# ProPrj_FLIGHT-CONTROLLER_2025-07-13-15-4.net
KiCad netlist of a schematic drawn in EasyEDA Pro
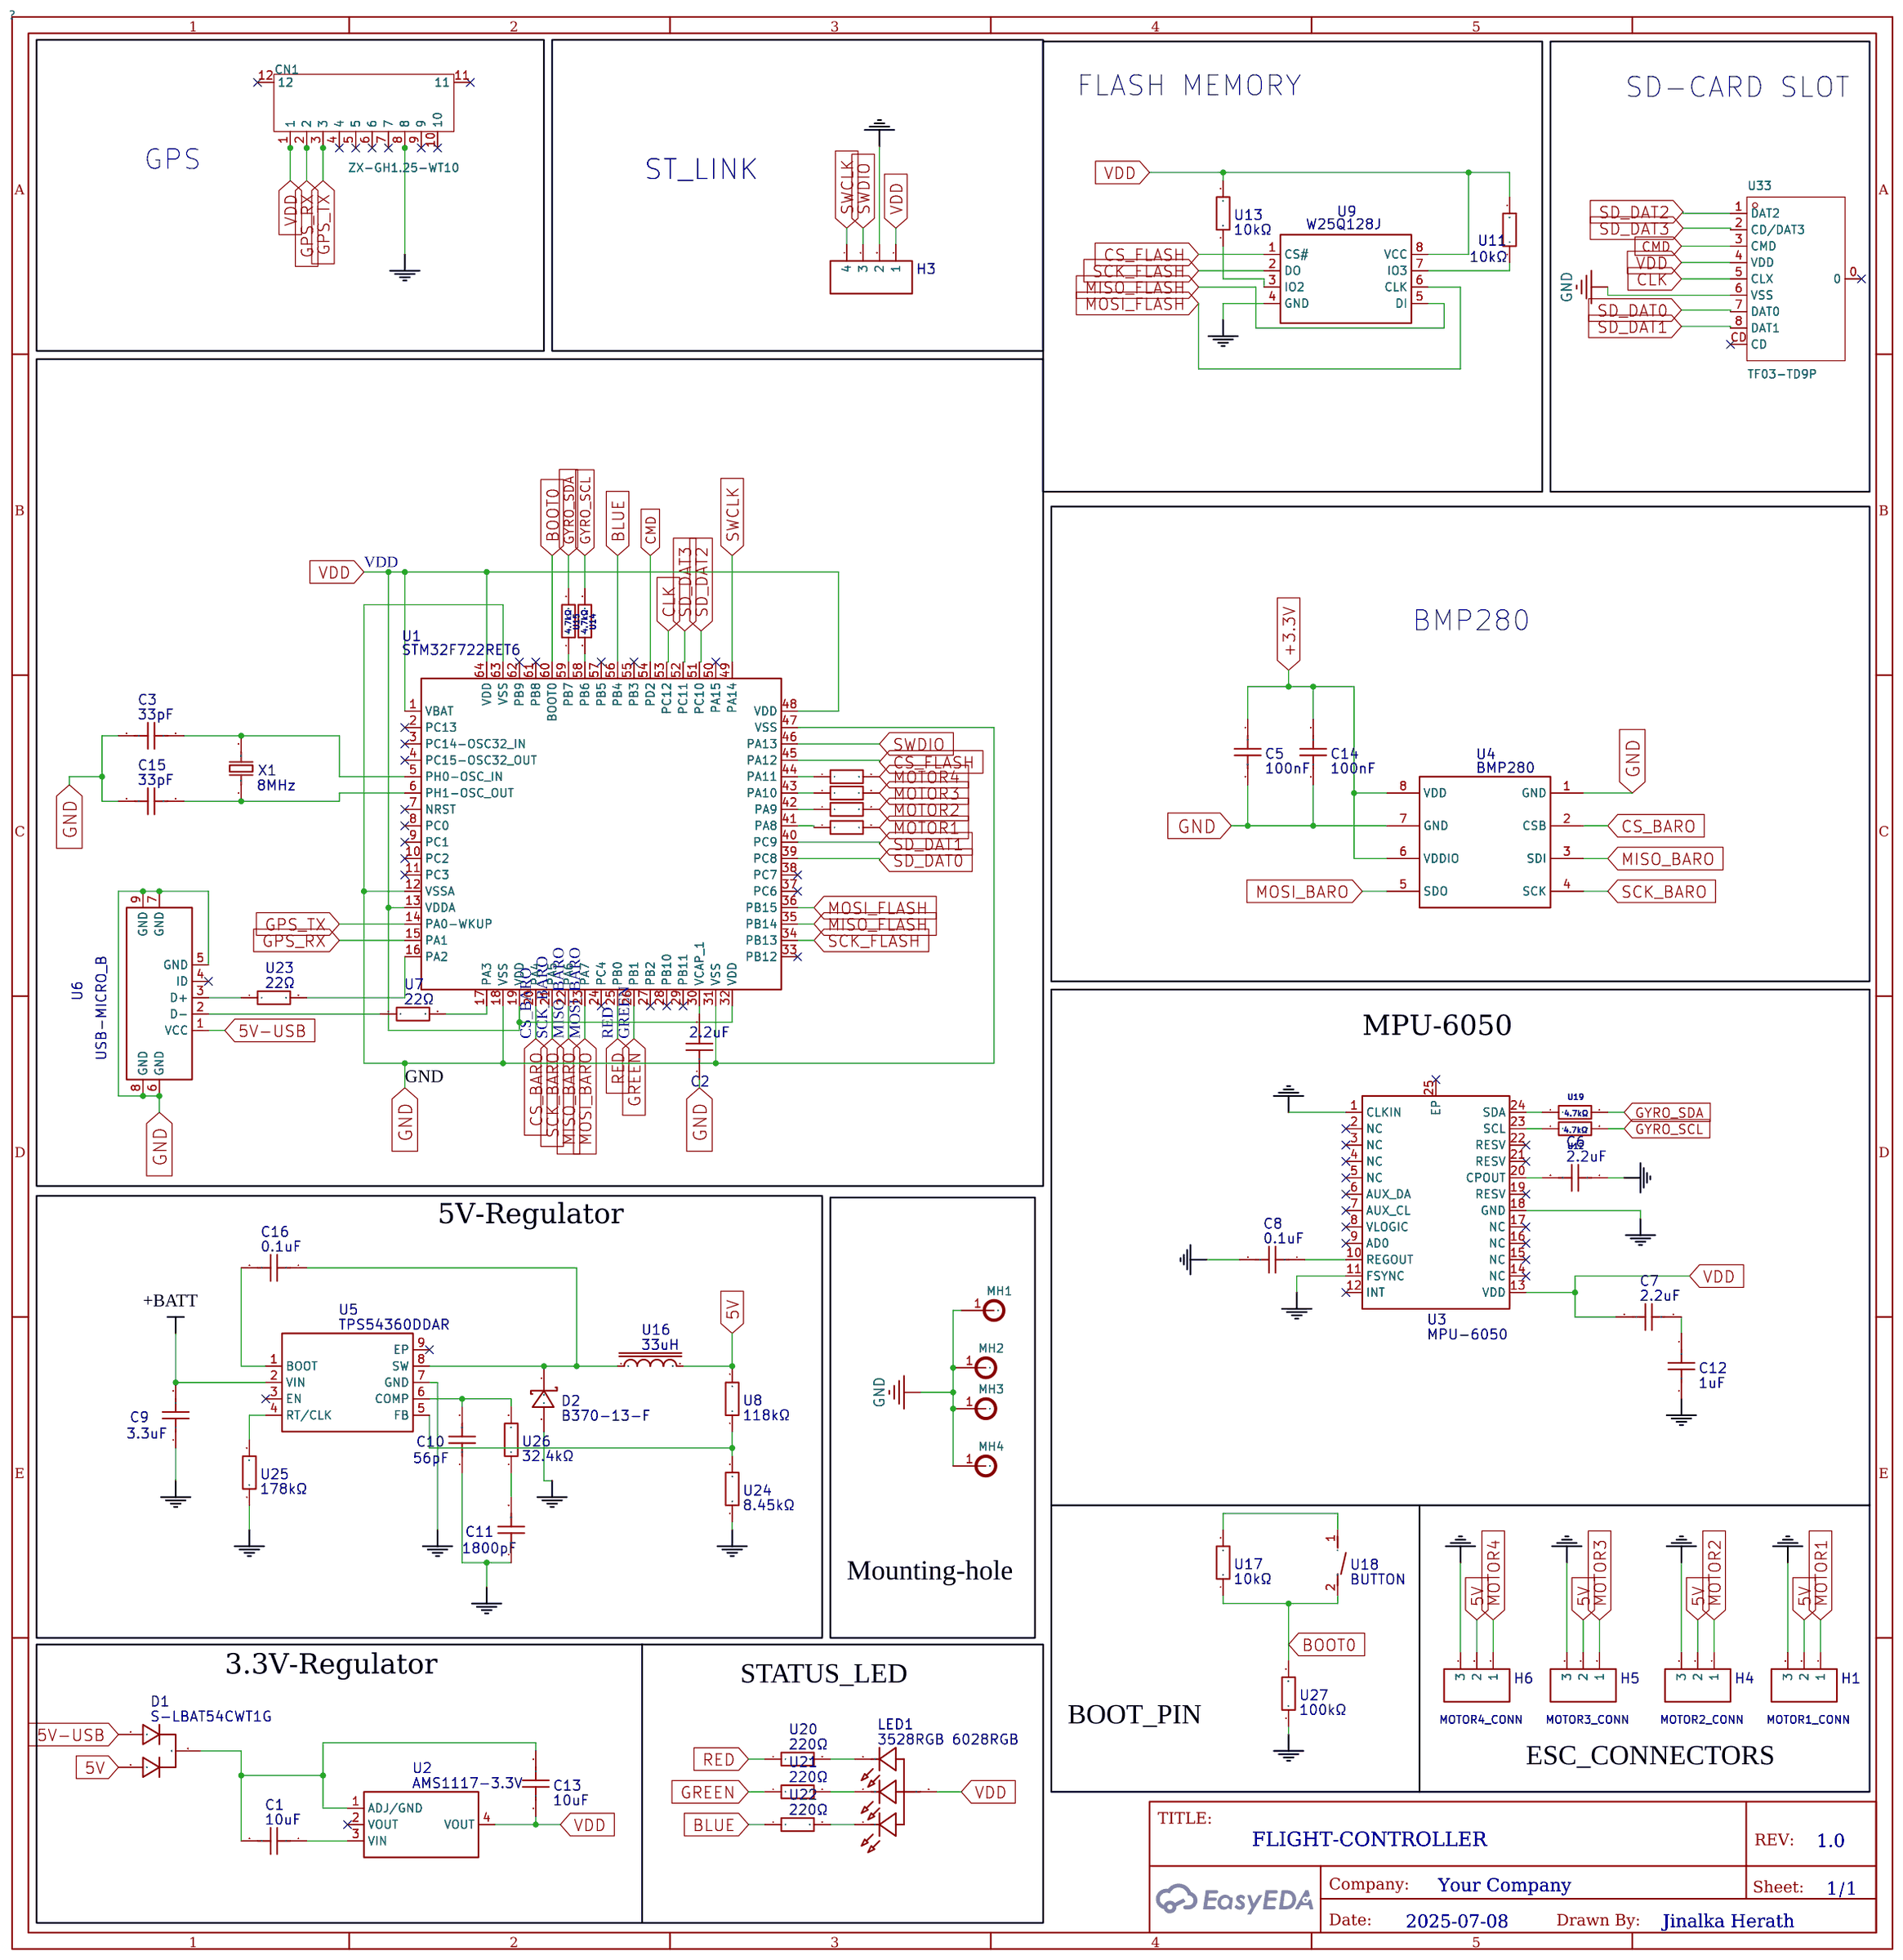
[diagram p0: schematic sheet]

(export (version "E")
  (design (tool "Eeschema 10.0.6"))
  (components
    (comp (ref "C1")
      (value "10uF")
      (footprint "easyedapro:C0603")
      (fields
        (field (name "Manufacturer Part") "C1608CH2A560J080AA")
        (field (name "Manufacturer") "TDK")
        (field (name "Contributor") "lcsc")
      )
      (libsource (lib "easyedapro") (part "10uF"))
    )
    (comp (ref "C2")
      (value "2.2uF")
      (footprint "easyedapro:CAP-SMD_L3.2-W2.5-1")
      (fields
        (field (name "Manufacturer Part") "25MU225MB23225")
        (field (name "Manufacturer") "rubycon(红宝石)")
        (field (name "Contributor") "lcsc")
      )
      (libsource (lib "easyedapro") (part "2.2uF"))
    )
    (comp (ref "C3")
      (value "33pF")
      (footprint "easyedapro:C0603")
      (fields
        (field (name "Manufacturer Part") "C1608CH2A560J080AA")
        (field (name "Manufacturer") "TDK")
        (field (name "Contributor") "lcsc")
      )
      (libsource (lib "easyedapro") (part "33pF"))
    )
    (comp (ref "C5")
      (value "100nF")
      (footprint "easyedapro:C0603")
      (fields
        (field (name "Manufacturer Part") "C1608CH2A560J080AA")
        (field (name "Manufacturer") "TDK")
        (field (name "Contributor") "lcsc")
      )
      (libsource (lib "easyedapro") (part "100nF"))
    )
    (comp (ref "C6")
      (value "2.2uF")
      (footprint "easyedapro:CAP-SMD_L3.2-W2.5-1")
      (fields
        (field (name "Manufacturer Part") "25MU225MB23225")
        (field (name "Manufacturer") "rubycon(红宝石)")
        (field (name "Contributor") "lcsc")
      )
      (libsource (lib "easyedapro") (part "2.2uF"))
    )
    (comp (ref "C7")
      (value "2.2uF")
      (footprint "easyedapro:CAP-SMD_L3.2-W2.5-1")
      (fields
        (field (name "Manufacturer Part") "25MU225MB23225")
        (field (name "Manufacturer") "rubycon(红宝石)")
        (field (name "Contributor") "lcsc")
      )
      (libsource (lib "easyedapro") (part "2.2uF"))
    )
    (comp (ref "C8")
      (value "0.1uF")
      (footprint "easyedapro:C0603")
      (fields
        (field (name "Manufacturer Part") "C1608CH2A560J080AA")
        (field (name "Manufacturer") "TDK")
        (field (name "Contributor") "lcsc")
      )
      (libsource (lib "easyedapro") (part "0.1uF"))
    )
    (comp (ref "C9")
      (value "3.3uF")
      (footprint "easyedapro:C0603")
      (fields
        (field (name "Manufacturer Part") "C1608CH2A560J080AA")
        (field (name "Manufacturer") "TDK")
        (field (name "Contributor") "lcsc")
      )
      (libsource (lib "easyedapro") (part "3.3uF"))
    )
    (comp (ref "C10")
      (value "56pF")
      (footprint "easyedapro:C0603")
      (fields
        (field (name "Manufacturer Part") "C1608CH2A560J080AA")
        (field (name "Manufacturer") "TDK")
        (field (name "Contributor") "lcsc")
      )
      (libsource (lib "easyedapro") (part "56pF"))
    )
    (comp (ref "C11")
      (value "1800pF")
      (footprint "easyedapro:C0603")
      (fields
        (field (name "Manufacturer Part") "C1608CH2A560J080AA")
        (field (name "Manufacturer") "TDK")
        (field (name "Contributor") "lcsc")
      )
      (libsource (lib "easyedapro") (part "1800pF"))
    )
    (comp (ref "C12")
      (value "1uF")
      (footprint "easyedapro:C0603")
      (fields
        (field (name "Manufacturer Part") "C1608CH2A560J080AA")
        (field (name "Manufacturer") "TDK")
        (field (name "Contributor") "lcsc")
      )
      (libsource (lib "easyedapro") (part "1uF"))
    )
    (comp (ref "C13")
      (value "10uF")
      (footprint "easyedapro:C0603")
      (fields
        (field (name "Manufacturer Part") "C1608CH2A560J080AA")
        (field (name "Manufacturer") "TDK")
        (field (name "Contributor") "lcsc")
      )
      (libsource (lib "easyedapro") (part "10uF"))
    )
    (comp (ref "C14")
      (value "100nF")
      (footprint "easyedapro:C0603")
      (fields
        (field (name "Manufacturer Part") "C1608CH2A560J080AA")
        (field (name "Manufacturer") "TDK")
        (field (name "Contributor") "lcsc")
      )
      (libsource (lib "easyedapro") (part "100nF"))
    )
    (comp (ref "C15")
      (value "33pF")
      (footprint "easyedapro:C0603")
      (fields
        (field (name "Manufacturer Part") "C1608CH2A560J080AA")
        (field (name "Manufacturer") "TDK")
        (field (name "Contributor") "lcsc")
      )
      (libsource (lib "easyedapro") (part "33pF"))
    )
    (comp (ref "C16")
      (value "0.1uF")
      (footprint "easyedapro:C0603")
      (fields
        (field (name "Manufacturer Part") "C1608CH2A560J080AA")
        (field (name "Manufacturer") "TDK")
        (field (name "Contributor") "lcsc")
      )
      (libsource (lib "easyedapro") (part "0.1uF"))
    )
    (comp (ref "CN1")
      (value "ZX-GH1.25-WT10")
      (footprint "easyedapro:CONN-SMD_ZX-GH1.25-WT10")
      (fields (field (name "Manufacturer") "Megastar(兆星)"))
      (libsource (lib "easyedapro") (part "ZX-GH1.25-WT10"))
    )
    (comp (ref "D1")
      (value "S-LBAT54CWT1G")
      (footprint "easyedapro:SC-70-3_L2.0-W1.3-P1.30-LS2.1-BR")
      (fields (field (name "Manufacturer") "LRC(乐山无线电)") (field (name "Contributor") "lcsc"))
      (libsource (lib "easyedapro") (part "S-LBAT54CWT1G"))
    )
    (comp (ref "D2")
      (value "B370-13-F")
      (footprint "easyedapro:SMC_L7.1-W6.2-LS8.1-RD")
      (fields (field (name "Manufacturer") "DIODES(美台)") (field (name "Contributor") "LCSC"))
      (libsource (lib "easyedapro") (part "B370-13-F"))
    )
    (comp (ref "H1")
      (value "MOTOR1_CONN")
      (footprint "easyedapro:HDR-F-2.54_1X3")
      (fields (field (name "Contributor") "LCEDA_Lib"))
      (libsource (lib "easyedapro") (part "MOTOR1_CONN"))
    )
    (comp (ref "H3")
      (value "ST_LINK")
      (footprint "easyedapro:HDR-F-2.54_1X4")
      (fields (field (name "Contributor") "LCEDA_Lib"))
      (libsource (lib "easyedapro") (part "ST_LINK"))
    )
    (comp (ref "H4")
      (value "MOTOR2_CONN")
      (footprint "easyedapro:HDR-F-2.54_1X3")
      (fields (field (name "Contributor") "LCEDA_Lib"))
      (libsource (lib "easyedapro") (part "MOTOR2_CONN"))
    )
    (comp (ref "H5")
      (value "MOTOR3_CONN")
      (footprint "easyedapro:HDR-F-2.54_1X3")
      (fields (field (name "Contributor") "LCEDA_Lib"))
      (libsource (lib "easyedapro") (part "MOTOR3_CONN"))
    )
    (comp (ref "H6")
      (value "MOTOR4_CONN")
      (footprint "easyedapro:HDR-F-2.54_1X3")
      (fields (field (name "Contributor") "LCEDA_Lib"))
      (libsource (lib "easyedapro") (part "MOTOR4_CONN"))
    )
    (comp (ref "LED1")
      (value "3528RGB 6028RGB")
      (footprint "easyedapro:LED-SMD_4P-L3.5-W2.8_3528RGB-6028RGB")
      (fields
        (field (name "Manufacturer Part") "3528反贴RGB 6028反贴RGB 缺口蓝色")
        (field (name "Contributor") "lcsc")
      )
      (libsource (lib "easyedapro") (part "3528RGB 6028RGB"))
    )
    (comp (ref "MH1")
      (value "~")
      (footprint "easyedapro:MH_7.5")
      (libsource (lib "easyedapro") (part "MH_7.5"))
    )
    (comp (ref "MH2")
      (value "~")
      (footprint "easyedapro:MH_7.5")
      (libsource (lib "easyedapro") (part "MH_7.5"))
    )
    (comp (ref "MH3")
      (value "~")
      (footprint "easyedapro:MH_7.5")
      (libsource (lib "easyedapro") (part "MH_7.5"))
    )
    (comp (ref "MH4")
      (value "~")
      (footprint "easyedapro:MH_7.5")
      (libsource (lib "easyedapro") (part "MH_7.5"))
    )
    (comp (ref "U1")
      (value "STM32F722RET6")
      (footprint "easyedapro:LQFP-64_L10.0-W10.0-P0.50-LS12.0-BL")
      (fields (field (name "Manufacturer") "ST(意法半导体)") (field (name "Contributor") "LCSC"))
      (libsource (lib "easyedapro") (part "STM32F722RET6"))
    )
    (comp (ref "U2")
      (value "AMS1117-3.3V")
      (footprint "easyedapro:SOT-223-4_L6.5-W3.5-P2.30-LS7.0-BR")
      (fields (field (name "Manufacturer") "WPMtek(维攀)") (field (name "Contributor") "LCSC"))
      (libsource (lib "easyedapro") (part "AMS1117-3.3V"))
    )
    (comp (ref "U3")
      (value "MPU-6050")
      (footprint "easyedapro:QFN-24_L4.0-W4.0-P0.50-BL-EP2.7")
      (fields (field (name "Manufacturer") "TDK InvenSense(应美盛)"))
      (libsource (lib "easyedapro") (part "MPU-6050_C24112"))
    )
    (comp (ref "U4")
      (value "BMP280")
      (footprint "easyedapro:LGA-8_L2.5-W2.0-P0.65_AMP6127")
      (fields (field (name "Manufacturer") "Bosch(博世)"))
      (libsource (lib "easyedapro") (part "BMP280"))
    )
    (comp (ref "U5")
      (value "TPS54360DDAR")
      (footprint "easyedapro:ESOP-8_L4.9-W3.9-P1.27-LS6.0-BL-EP")
      (fields
        (field (name "Manufacturer Part") "TPS54360DDAR(TOKMAS)")
        (field (name "Manufacturer") "Tokmas(托克马斯)")
        (field (name "Contributor") "lcsc")
      )
      (libsource (lib "easyedapro") (part "TPS54360DDAR(TOKMAS)"))
    )
    (comp (ref "U6")
      (value "USB-MICRO_B")
      (footprint "easyedapro:MICRO-USB-SMD_USB-MICRO_B")
      (fields (field (name "Contributor") "LCSC"))
      (libsource (lib "easyedapro") (part "USB-MICRO_B"))
    )
    (comp (ref "U7")
      (value "22Ω")
      (footprint "easyedapro:RES-TH_BD2.3-L3.7-P7.70-D0.9")
      (fields
        (field (name "Manufacturer Part") "MF1/8W-220Ω±1%-ST52")
        (field (name "Manufacturer") "VO(翔胜)")
        (field (name "Contributor") "lcsc")
      )
      (libsource (lib "easyedapro") (part "22Ω"))
    )
    (comp (ref "U8")
      (value "118kΩ")
      (footprint "easyedapro:RES-TH_BD2.3-L3.7-P7.70-D0.9")
      (fields
        (field (name "Manufacturer Part") "MF1/8W-220Ω±1%-ST52")
        (field (name "Manufacturer") "VO(翔胜)")
        (field (name "Contributor") "lcsc")
      )
      (libsource (lib "easyedapro") (part "118kΩ"))
    )
    (comp (ref "U9")
      (value "W25Q128J")
      (footprint "easyedapro:SOIC-8_L5.3-W5.3-P1.27-LS8.0-BL")
      (fields (field (name "Manufacturer Part") "W25Q128JVSIQ") (field (name "Manufacturer") "WINBOND(华邦)"))
      (libsource (lib "easyedapro") (part "W25Q128JVSIQTR"))
    )
    (comp (ref "U11")
      (value "10kΩ")
      (footprint "easyedapro:RES-TH_BD2.3-L3.7-P7.70-D0.9")
      (fields
        (field (name "Manufacturer Part") "MF1/8W-220Ω±1%-ST52")
        (field (name "Manufacturer") "VO(翔胜)")
        (field (name "Contributor") "lcsc")
      )
      (libsource (lib "easyedapro") (part "10kΩ"))
    )
    (comp (ref "U12")
      (value "4.7kΩ")
      (footprint "easyedapro:RES-TH_BD2.3-L3.7-P7.70-D0.9")
      (fields
        (field (name "Manufacturer Part") "MF1/8W-220Ω±1%-ST52")
        (field (name "Manufacturer") "VO(翔胜)")
        (field (name "Contributor") "lcsc")
      )
      (libsource (lib "easyedapro") (part "4.7kΩ"))
    )
    (comp (ref "U13")
      (value "10kΩ")
      (footprint "easyedapro:RES-TH_BD2.3-L3.7-P7.70-D0.9")
      (fields
        (field (name "Manufacturer Part") "MF1/8W-220Ω±1%-ST52")
        (field (name "Manufacturer") "VO(翔胜)")
        (field (name "Contributor") "lcsc")
      )
      (libsource (lib "easyedapro") (part "10kΩ"))
    )
    (comp (ref "U14")
      (value "4.7kΩ")
      (footprint "easyedapro:RES-TH_BD2.3-L3.7-P7.70-D0.9")
      (fields
        (field (name "Manufacturer Part") "MF1/8W-220Ω±1%-ST52")
        (field (name "Manufacturer") "VO(翔胜)")
        (field (name "Contributor") "lcsc")
      )
      (libsource (lib "") (part "4.7kΩ_1"))
    )
    (comp (ref "U15")
      (value "4.7kΩ")
      (footprint "easyedapro:RES-TH_BD2.3-L3.7-P7.70-D0.9")
      (fields
        (field (name "Manufacturer Part") "MF1/8W-220Ω±1%-ST52")
        (field (name "Manufacturer") "VO(翔胜)")
        (field (name "Contributor") "lcsc")
      )
      (libsource (lib "") (part "4.7kΩ_1"))
    )
    (comp (ref "U16")
      (value "33uH")
      (footprint "easyedapro:IND-SMD_L8.5-W8.0_SMS0850")
      (fields
        (field (name "Manufacturer Part") "SMS0850-330MT")
        (field (name "Manufacturer") "LanTu Micro(蓝图微电)")
        (field (name "Contributor") "lcsc")
      )
      (libsource (lib "easyedapro") (part "33uH"))
    )
    (comp (ref "U17")
      (value "10kΩ")
      (footprint "easyedapro:RES-TH_BD2.3-L3.7-P7.70-D0.9")
      (fields
        (field (name "Manufacturer Part") "MF1/8W-220Ω±1%-ST52")
        (field (name "Manufacturer") "VO(翔胜)")
        (field (name "Contributor") "lcsc")
      )
      (libsource (lib "easyedapro") (part "10kΩ"))
    )
    (comp (ref "U18")
      (value "BUTTON")
      (footprint "easyedapro:KEY-SMD_L6.0-W6.0-LS6.6")
      (fields (field (name "Contributor") "lcsc"))
      (libsource (lib "easyedapro") (part "BUTTON"))
    )
    (comp (ref "U19")
      (value "4.7kΩ")
      (footprint "easyedapro:RES-TH_BD2.3-L3.7-P7.70-D0.9")
      (fields
        (field (name "Manufacturer Part") "MF1/8W-220Ω±1%-ST52")
        (field (name "Manufacturer") "VO(翔胜)")
        (field (name "Contributor") "lcsc")
      )
      (libsource (lib "easyedapro") (part "4.7kΩ"))
    )
    (comp (ref "U20")
      (value "220Ω")
      (footprint "easyedapro:RES-TH_BD2.3-L3.7-P7.70-D0.9")
      (fields
        (field (name "Manufacturer Part") "MF1/8W-220Ω±1%-ST52")
        (field (name "Manufacturer") "VO(翔胜)")
        (field (name "Contributor") "lcsc")
      )
      (libsource (lib "easyedapro") (part "220Ω"))
    )
    (comp (ref "U21")
      (value "220Ω")
      (footprint "easyedapro:RES-TH_BD2.3-L3.7-P7.70-D0.9")
      (fields
        (field (name "Manufacturer Part") "MF1/8W-220Ω±1%-ST52")
        (field (name "Manufacturer") "VO(翔胜)")
        (field (name "Contributor") "lcsc")
      )
      (libsource (lib "easyedapro") (part "220Ω"))
    )
    (comp (ref "U22")
      (value "220Ω")
      (footprint "easyedapro:RES-TH_BD2.3-L3.7-P7.70-D0.9")
      (fields
        (field (name "Manufacturer Part") "MF1/8W-220Ω±1%-ST52")
        (field (name "Manufacturer") "VO(翔胜)")
        (field (name "Contributor") "lcsc")
      )
      (libsource (lib "easyedapro") (part "220Ω"))
    )
    (comp (ref "U23")
      (value "22Ω")
      (footprint "easyedapro:RES-TH_BD2.3-L3.7-P7.70-D0.9")
      (fields
        (field (name "Manufacturer Part") "MF1/8W-220Ω±1%-ST52")
        (field (name "Manufacturer") "VO(翔胜)")
        (field (name "Contributor") "lcsc")
      )
      (libsource (lib "easyedapro") (part "22Ω"))
    )
    (comp (ref "U24")
      (value "8.45kΩ")
      (footprint "easyedapro:RES-TH_BD2.3-L3.7-P7.70-D0.9")
      (fields
        (field (name "Manufacturer Part") "MF1/8W-220Ω±1%-ST52")
        (field (name "Manufacturer") "VO(翔胜)")
        (field (name "Contributor") "lcsc")
      )
      (libsource (lib "easyedapro") (part "8.45kΩ"))
    )
    (comp (ref "U25")
      (value "178kΩ")
      (footprint "easyedapro:RES-TH_BD2.3-L3.7-P7.70-D0.9")
      (fields
        (field (name "Manufacturer Part") "MF1/8W-220Ω±1%-ST52")
        (field (name "Manufacturer") "VO(翔胜)")
        (field (name "Contributor") "lcsc")
      )
      (libsource (lib "easyedapro") (part "178kΩ"))
    )
    (comp (ref "U26")
      (value "32.4kΩ")
      (footprint "easyedapro:RES-TH_BD2.3-L3.7-P7.70-D0.9")
      (fields
        (field (name "Manufacturer Part") "MF1/8W-220Ω±1%-ST52")
        (field (name "Manufacturer") "VO(翔胜)")
        (field (name "Contributor") "lcsc")
      )
      (libsource (lib "easyedapro") (part "32.4kΩ"))
    )
    (comp (ref "U27")
      (value "100kΩ")
      (footprint "easyedapro:RES-TH_BD2.3-L3.7-P7.70-D0.9")
      (fields
        (field (name "Manufacturer Part") "MF1/8W-220Ω±1%-ST52")
        (field (name "Manufacturer") "VO(翔胜)")
        (field (name "Contributor") "lcsc")
      )
      (libsource (lib "easyedapro") (part "100kΩ"))
    )
    (comp (ref "U28")
      (value "100Ω")
      (footprint "easyedapro:RES-TH_BD2.3-L3.7-P7.70-D0.9")
      (fields
        (field (name "Manufacturer Part") "MF1/8W-220Ω±1%-ST52")
        (field (name "Manufacturer") "VO(翔胜)")
        (field (name "Contributor") "lcsc")
      )
      (libsource (lib "easyedapro") (part "100Ω"))
    )
    (comp (ref "U29")
      (value "100Ω")
      (footprint "easyedapro:RES-TH_BD2.3-L3.7-P7.70-D0.9")
      (fields
        (field (name "Manufacturer Part") "MF1/8W-220Ω±1%-ST52")
        (field (name "Manufacturer") "VO(翔胜)")
        (field (name "Contributor") "lcsc")
      )
      (libsource (lib "easyedapro") (part "100Ω"))
    )
    (comp (ref "U30")
      (value "100Ω")
      (footprint "easyedapro:RES-TH_BD2.3-L3.7-P7.70-D0.9")
      (fields
        (field (name "Manufacturer Part") "MF1/8W-220Ω±1%-ST52")
        (field (name "Manufacturer") "VO(翔胜)")
        (field (name "Contributor") "lcsc")
      )
      (libsource (lib "easyedapro") (part "100Ω"))
    )
    (comp (ref "U33")
      (value "TF03-TD9P")
      (footprint "easyedapro:CONN-SMD_TF-001A-P")
      (fields (field (name "Manufacturer") "BXCONN(宝讯)"))
      (libsource (lib "easyedapro") (part "TF03-TD9P"))
    )
    (comp (ref "U34")
      (value "100Ω")
      (footprint "easyedapro:RES-TH_BD2.3-L3.7-P7.70-D0.9")
      (fields
        (field (name "Manufacturer Part") "MF1/8W-220Ω±1%-ST52")
        (field (name "Manufacturer") "VO(翔胜)")
        (field (name "Contributor") "lcsc")
      )
      (libsource (lib "easyedapro") (part "100Ω"))
    )
    (comp (ref "X1")
      (value "8MHz")
      (footprint "easyedapro:CRYSTAL-SMD_L3.2-W2.5_3225-8MHZ")
      (fields
        (field (name "Manufacturer Part") "X22EL89COI-111YLC-8M")
        (field (name "Manufacturer") "YXC(扬兴晶振)")
        (field (name "Contributor") "lcsc")
      )
      (libsource (lib "easyedapro") (part "8MHz"))
    )
  )
  (nets
    (net (code "1") (name "+3.3V") (class "Default")
      (node (ref "C14") (pin "1") (pinfunction "1_1") (pintype "unspecified"))
      (node (ref "C5") (pin "1") (pinfunction "1_1") (pintype "unspecified"))
      (node (ref "U4") (pin "6") (pinfunction "VDDIO_6") (pintype "unspecified"))
      (node (ref "U4") (pin "8") (pinfunction "VDD_8") (pintype "unspecified"))
    )
    (net (code "2") (name "+BATT") (class "Default")
      (node (ref "C9") (pin "2") (pinfunction "2_2") (pintype "unspecified"))
      (node (ref "U5") (pin "2") (pinfunction "VIN_2") (pintype "unspecified"))
    )
    (net (code "3") (name "5V") (class "Default")
      (node (ref "D1") (pin "2") (pinfunction "2_2") (pintype "unspecified"))
      (node (ref "H1") (pin "2") (pinfunction "2_2") (pintype "input"))
      (node (ref "H4") (pin "2") (pinfunction "2_2") (pintype "input"))
      (node (ref "H5") (pin "2") (pinfunction "2_2") (pintype "input"))
      (node (ref "H6") (pin "2") (pinfunction "2_2") (pintype "input"))
      (node (ref "U16") (pin "2") (pinfunction "2_2") (pintype "unspecified"))
      (node (ref "U8") (pin "2") (pinfunction "2_2") (pintype "unspecified"))
    )
    (net (code "4") (name "5V-USB") (class "Default")
      (node (ref "D1") (pin "1") (pinfunction "1_1") (pintype "unspecified"))
      (node (ref "U6") (pin "1") (pinfunction "VCC_1") (pintype "unspecified"))
    )
    (net (code "5") (name "BLUE") (class "Default")
      (node (ref "U1") (pin "56") (pinfunction "PB4_56") (pintype "unspecified"))
      (node (ref "U22") (pin "1") (pinfunction "1_1") (pintype "unspecified"))
    )
    (net (code "6") (name "BOOT0") (class "Default")
      (node (ref "U1") (pin "60") (pinfunction "BOOT0_60") (pintype "unspecified"))
      (node (ref "U17") (pin "1") (pinfunction "1_1") (pintype "unspecified"))
      (node (ref "U18") (pin "2") (pinfunction "B_2") (pintype "unspecified"))
      (node (ref "U27") (pin "2") (pinfunction "2_2") (pintype "unspecified"))
    )
    (net (code "7") (name "CLK") (class "Default")
      (node (ref "U1") (pin "53") (pinfunction "PC12_53") (pintype "unspecified"))
      (node (ref "U33") (pin "5") (pinfunction "CLX_5") (pintype "unspecified"))
    )
    (net (code "8") (name "CMD") (class "Default")
      (node (ref "U1") (pin "54") (pinfunction "PD2_54") (pintype "unspecified"))
      (node (ref "U33") (pin "3") (pinfunction "CMD_3") (pintype "unspecified"))
    )
    (net (code "9") (name "CS_BARO") (class "Default")
      (node (ref "U1") (pin "20") (pinfunction "PA4_20") (pintype "unspecified"))
      (node (ref "U4") (pin "2") (pinfunction "CSB_2") (pintype "unspecified"))
    )
    (net (code "10") (name "CS_FLASH") (class "Default")
      (node (ref "U1") (pin "45") (pinfunction "PA12_45") (pintype "unspecified"))
      (node (ref "U9") (pin "1") (pinfunction "CS#_1") (pintype "unspecified"))
    )
    (net (code "11") (name "GND") (class "Default")
      (node (ref "C10") (pin "1") (pinfunction "1_1") (pintype "unspecified"))
      (node (ref "C11") (pin "1") (pinfunction "1_1") (pintype "unspecified"))
      (node (ref "C12") (pin "2") (pinfunction "2_2") (pintype "unspecified"))
      (node (ref "C14") (pin "2") (pinfunction "2_2") (pintype "unspecified"))
      (node (ref "C15") (pin "1") (pinfunction "1_1") (pintype "unspecified"))
      (node (ref "C2") (pin "1") (pinfunction "1_1") (pintype "unspecified"))
      (node (ref "C3") (pin "1") (pinfunction "1_1") (pintype "unspecified"))
      (node (ref "C5") (pin "2") (pinfunction "2_2") (pintype "unspecified"))
      (node (ref "C6") (pin "1") (pinfunction "1_1") (pintype "unspecified"))
      (node (ref "C8") (pin "2") (pinfunction "2_2") (pintype "unspecified"))
      (node (ref "C9") (pin "1") (pinfunction "1_1") (pintype "unspecified"))
      (node (ref "CN1") (pin "8") (pinfunction "8_8") (pintype "unspecified"))
      (node (ref "D2") (pin "2") (pinfunction "A_2") (pintype "unspecified"))
      (node (ref "H1") (pin "3") (pinfunction "3_3") (pintype "input"))
      (node (ref "H3") (pin "2") (pinfunction "2_2") (pintype "unspecified"))
      (node (ref "H4") (pin "3") (pinfunction "3_3") (pintype "input"))
      (node (ref "H5") (pin "3") (pinfunction "3_3") (pintype "input"))
      (node (ref "H6") (pin "3") (pinfunction "3_3") (pintype "input"))
      (node (ref "MH1") (pin "1") (pinfunction "1_1") (pintype "input"))
      (node (ref "MH2") (pin "1") (pinfunction "1_1") (pintype "input"))
      (node (ref "MH3") (pin "1") (pinfunction "1_1") (pintype "input"))
      (node (ref "MH4") (pin "1") (pinfunction "1_1") (pintype "input"))
      (node (ref "U1") (pin "12") (pinfunction "VSSA_12") (pintype "unspecified"))
      (node (ref "U1") (pin "18") (pinfunction "VSS_18") (pintype "unspecified"))
      (node (ref "U1") (pin "31") (pinfunction "VSS_31") (pintype "unspecified"))
      (node (ref "U1") (pin "47") (pinfunction "VSS_47") (pintype "unspecified"))
      (node (ref "U1") (pin "63") (pinfunction "VSS_63") (pintype "unspecified"))
      (node (ref "U24") (pin "1") (pinfunction "1_1") (pintype "unspecified"))
      (node (ref "U25") (pin "1") (pinfunction "1_1") (pintype "unspecified"))
      (node (ref "U27") (pin "1") (pinfunction "1_1") (pintype "unspecified"))
      (node (ref "U3") (pin "1") (pinfunction "CLKIN_1") (pintype "unspecified"))
      (node (ref "U3") (pin "11") (pinfunction "FSYNC_11") (pintype "unspecified"))
      (node (ref "U3") (pin "18") (pinfunction "GND_18") (pintype "unspecified"))
      (node (ref "U33") (pin "6") (pinfunction "VSS_6") (pintype "unspecified"))
      (node (ref "U4") (pin "1") (pinfunction "GND_1") (pintype "unspecified"))
      (node (ref "U4") (pin "7") (pinfunction "GND_7") (pintype "unspecified"))
      (node (ref "U5") (pin "7") (pinfunction "GND_7") (pintype "unspecified"))
      (node (ref "U6") (pin "5") (pinfunction "GND_5") (pintype "unspecified"))
      (node (ref "U6") (pin "6") (pinfunction "GND_6") (pintype "unspecified"))
      (node (ref "U6") (pin "7") (pinfunction "GND_7") (pintype "unspecified"))
      (node (ref "U6") (pin "8") (pinfunction "GND_8") (pintype "unspecified"))
      (node (ref "U6") (pin "9") (pinfunction "GND_9") (pintype "unspecified"))
      (node (ref "U9") (pin "4") (pinfunction "GND_4") (pintype "unspecified"))
    )
    (net (code "12") (name "GPS_RX") (class "Default")
      (node (ref "CN1") (pin "2") (pinfunction "2_2") (pintype "unspecified"))
      (node (ref "U1") (pin "15") (pinfunction "PA1_15") (pintype "unspecified"))
    )
    (net (code "13") (name "GPS_TX") (class "Default")
      (node (ref "CN1") (pin "3") (pinfunction "3_3") (pintype "unspecified"))
      (node (ref "U1") (pin "14") (pinfunction "PA0-WKUP_14") (pintype "unspecified"))
    )
    (net (code "14") (name "GREEN") (class "Default")
      (node (ref "U1") (pin "26") (pinfunction "PB1_26") (pintype "unspecified"))
      (node (ref "U21") (pin "1") (pinfunction "1_1") (pintype "unspecified"))
    )
    (net (code "15") (name "GYRO_SCL") (class "Default")
      (node (ref "U12") (pin "2") (pinfunction "2_2") (pintype "unspecified"))
      (node (ref "U14") (pin "2") (pinfunction "2_2") (pintype "unspecified"))
    )
    (net (code "16") (name "GYRO_SDA") (class "Default")
      (node (ref "U15") (pin "2") (pinfunction "2_2") (pintype "unspecified"))
      (node (ref "U19") (pin "2") (pinfunction "2_2") (pintype "unspecified"))
    )
    (net (code "17") (name "MISO_BARO") (class "Default")
      (node (ref "U1") (pin "22") (pinfunction "PA6_22") (pintype "unspecified"))
      (node (ref "U4") (pin "3") (pinfunction "SDI_3") (pintype "unspecified"))
    )
    (net (code "18") (name "MISO_FLASH") (class "Default")
      (node (ref "U1") (pin "35") (pinfunction "PB14_35") (pintype "unspecified"))
      (node (ref "U9") (pin "5") (pinfunction "DI_5") (pintype "unspecified"))
    )
    (net (code "19") (name "MOSI_BARO") (class "Default")
      (node (ref "U1") (pin "23") (pinfunction "PA7_23") (pintype "unspecified"))
      (node (ref "U4") (pin "5") (pinfunction "SDO_5") (pintype "unspecified"))
    )
    (net (code "20") (name "MOSI_FLASH") (class "Default")
      (node (ref "U1") (pin "36") (pinfunction "PB15_36") (pintype "unspecified"))
      (node (ref "U9") (pin "6") (pinfunction "CLK_6") (pintype "unspecified"))
    )
    (net (code "21") (name "MOTOR1") (class "Default")
      (node (ref "H1") (pin "1") (pinfunction "1_1") (pintype "input"))
      (node (ref "U34") (pin "2") (pinfunction "2_2") (pintype "unspecified"))
    )
    (net (code "22") (name "MOTOR2") (class "Default")
      (node (ref "H4") (pin "1") (pinfunction "1_1") (pintype "input"))
      (node (ref "U29") (pin "2") (pinfunction "2_2") (pintype "unspecified"))
    )
    (net (code "23") (name "MOTOR3") (class "Default")
      (node (ref "H5") (pin "1") (pinfunction "1_1") (pintype "input"))
      (node (ref "U28") (pin "2") (pinfunction "2_2") (pintype "unspecified"))
    )
    (net (code "24") (name "MOTOR4") (class "Default")
      (node (ref "H6") (pin "1") (pinfunction "1_1") (pintype "input"))
      (node (ref "U30") (pin "2") (pinfunction "2_2") (pintype "unspecified"))
    )
    (net (code "25") (name "Net-(C11-Pad2)") (class "Default")
      (node (ref "C11") (pin "2") (pinfunction "2_2") (pintype "unspecified"))
      (node (ref "U26") (pin "1") (pinfunction "1_1") (pintype "unspecified"))
    )
    (net (code "26") (name "Net-(C12-Pad1)") (class "Default")
      (node (ref "C12") (pin "1") (pinfunction "1_1") (pintype "unspecified"))
      (node (ref "C7") (pin "1") (pinfunction "1_1") (pintype "unspecified"))
    )
    (net (code "27") (name "Net-(D2-C)") (class "Default")
      (node (ref "C16") (pin "1") (pinfunction "1_1") (pintype "unspecified"))
      (node (ref "D2") (pin "1") (pinfunction "C_1") (pintype "unspecified"))
      (node (ref "U16") (pin "1") (pinfunction "1_1") (pintype "unspecified"))
      (node (ref "U5") (pin "8") (pinfunction "SW_8") (pintype "unspecified"))
    )
    (net (code "28") (name "Net-(LED1-B)") (class "Default")
      (node (ref "LED1") (pin "1") (pinfunction "B_1") (pintype "unspecified"))
      (node (ref "U21") (pin "2") (pinfunction "2_2") (pintype "unspecified"))
    )
    (net (code "29") (name "Net-(LED1-G)") (class "Default")
      (node (ref "LED1") (pin "4") (pinfunction "G_4") (pintype "unspecified"))
      (node (ref "U22") (pin "2") (pinfunction "2_2") (pintype "unspecified"))
    )
    (net (code "30") (name "Net-(LED1-R)") (class "Default")
      (node (ref "LED1") (pin "2") (pinfunction "R_2") (pintype "unspecified"))
      (node (ref "U20") (pin "2") (pinfunction "2_2") (pintype "unspecified"))
    )
    (net (code "31") (name "Net-(U1-PA2)") (class "Default")
      (node (ref "U1") (pin "16") (pinfunction "PA2_16") (pintype "unspecified"))
      (node (ref "U23") (pin "2") (pinfunction "2_2") (pintype "unspecified"))
    )
    (net (code "32") (name "Net-(U1-PA3)") (class "Default")
      (node (ref "U1") (pin "17") (pinfunction "PA3_17") (pintype "unspecified"))
      (node (ref "U7") (pin "2") (pinfunction "2_2") (pintype "unspecified"))
    )
    (net (code "33") (name "Net-(U1-PA8)") (class "Default")
      (node (ref "U1") (pin "41") (pinfunction "PA8_41") (pintype "unspecified"))
      (node (ref "U34") (pin "1") (pinfunction "1_1") (pintype "unspecified"))
    )
    (net (code "34") (name "Net-(U1-PA9)") (class "Default")
      (node (ref "U1") (pin "42") (pinfunction "PA9_42") (pintype "unspecified"))
      (node (ref "U29") (pin "1") (pinfunction "1_1") (pintype "unspecified"))
    )
    (net (code "35") (name "Net-(U1-PA10)") (class "Default")
      (node (ref "U1") (pin "43") (pinfunction "PA10_43") (pintype "unspecified"))
      (node (ref "U28") (pin "1") (pinfunction "1_1") (pintype "unspecified"))
    )
    (net (code "36") (name "Net-(U1-PA11)") (class "Default")
      (node (ref "U1") (pin "44") (pinfunction "PA11_44") (pintype "unspecified"))
      (node (ref "U30") (pin "1") (pinfunction "1_1") (pintype "unspecified"))
    )
    (net (code "37") (name "Net-(U1-PB6)") (class "Default")
      (node (ref "U1") (pin "58") (pinfunction "PB6_58") (pintype "unspecified"))
      (node (ref "U14") (pin "1") (pinfunction "1_1") (pintype "unspecified"))
    )
    (net (code "38") (name "Net-(U1-PB7)") (class "Default")
      (node (ref "U1") (pin "59") (pinfunction "PB7_59") (pintype "unspecified"))
      (node (ref "U15") (pin "1") (pinfunction "1_1") (pintype "unspecified"))
    )
    (net (code "39") (name "Net-(U1-PH0-OSC_IN)") (class "Default")
      (node (ref "C3") (pin "2") (pinfunction "2_2") (pintype "unspecified"))
      (node (ref "U1") (pin "5") (pinfunction "PH0-OSC_IN_5") (pintype "unspecified"))
      (node (ref "X1") (pin "2") (pinfunction "2_2") (pintype "unspecified"))
    )
    (net (code "40") (name "Net-(U1-PH1-OSC_OUT)") (class "Default")
      (node (ref "C15") (pin "2") (pinfunction "2_2") (pintype "unspecified"))
      (node (ref "U1") (pin "6") (pinfunction "PH1-OSC_OUT_6") (pintype "unspecified"))
      (node (ref "X1") (pin "1") (pinfunction "1_1") (pintype "unspecified"))
    )
    (net (code "41") (name "Net-(U1-VCAP_1)") (class "Default")
      (node (ref "C2") (pin "2") (pinfunction "2_2") (pintype "unspecified"))
      (node (ref "U1") (pin "30") (pinfunction "VCAP_1_30") (pintype "unspecified"))
    )
    (net (code "42") (name "Net-(U2-ADJ{slash}GND)") (class "Default")
      (node (ref "C1") (pin "2") (pinfunction "2_2") (pintype "unspecified"))
      (node (ref "C13") (pin "1") (pinfunction "1_1") (pintype "unspecified"))
      (node (ref "D1") (pin "3") (pinfunction "3_3") (pintype "unspecified"))
      (node (ref "U2") (pin "1") (pinfunction "ADJ/GND_1") (pintype "unspecified"))
    )
    (net (code "43") (name "Net-(U2-VIN)") (class "Default")
      (node (ref "C1") (pin "1") (pinfunction "1_1") (pintype "unspecified"))
      (node (ref "U2") (pin "3") (pinfunction "VIN_3") (pintype "unspecified"))
    )
    (net (code "44") (name "Net-(U3-CPOUT)") (class "Default")
      (node (ref "C6") (pin "2") (pinfunction "2_2") (pintype "unspecified"))
      (node (ref "U3") (pin "20") (pinfunction "CPOUT_20") (pintype "unspecified"))
    )
    (net (code "45") (name "Net-(U3-REGOUT)") (class "Default")
      (node (ref "C8") (pin "1") (pinfunction "1_1") (pintype "unspecified"))
      (node (ref "U3") (pin "10") (pinfunction "REGOUT_10") (pintype "unspecified"))
    )
    (net (code "46") (name "Net-(U3-SCL)") (class "Default")
      (node (ref "U12") (pin "1") (pinfunction "1_1") (pintype "unspecified"))
      (node (ref "U3") (pin "23") (pinfunction "SCL_23") (pintype "unspecified"))
    )
    (net (code "47") (name "Net-(U3-SDA)") (class "Default")
      (node (ref "U19") (pin "1") (pinfunction "1_1") (pintype "unspecified"))
      (node (ref "U3") (pin "24") (pinfunction "SDA_24") (pintype "unspecified"))
    )
    (net (code "48") (name "Net-(U5-BOOT)") (class "Default")
      (node (ref "C16") (pin "2") (pinfunction "2_2") (pintype "unspecified"))
      (node (ref "U5") (pin "1") (pinfunction "BOOT_1") (pintype "unspecified"))
    )
    (net (code "49") (name "Net-(U5-COMP)") (class "Default")
      (node (ref "C10") (pin "2") (pinfunction "2_2") (pintype "unspecified"))
      (node (ref "U26") (pin "2") (pinfunction "2_2") (pintype "unspecified"))
      (node (ref "U5") (pin "6") (pinfunction "COMP_6") (pintype "unspecified"))
    )
    (net (code "50") (name "Net-(U5-FB)") (class "Default")
      (node (ref "U24") (pin "2") (pinfunction "2_2") (pintype "unspecified"))
      (node (ref "U5") (pin "5") (pinfunction "FB_5") (pintype "unspecified"))
      (node (ref "U8") (pin "1") (pinfunction "1_1") (pintype "unspecified"))
    )
    (net (code "51") (name "Net-(U5-RT{slash}CLK)") (class "Default")
      (node (ref "U25") (pin "2") (pinfunction "2_2") (pintype "unspecified"))
      (node (ref "U5") (pin "4") (pinfunction "RT/CLK_4") (pintype "unspecified"))
    )
    (net (code "52") (name "Net-(U6-D+)") (class "Default")
      (node (ref "U23") (pin "1") (pinfunction "1_1") (pintype "unspecified"))
      (node (ref "U6") (pin "3") (pinfunction "D+_3") (pintype "unspecified"))
    )
    (net (code "53") (name "Net-(U6-D-)") (class "Default")
      (node (ref "U6") (pin "2") (pinfunction "D-_2") (pintype "unspecified"))
      (node (ref "U7") (pin "1") (pinfunction "1_1") (pintype "unspecified"))
    )
    (net (code "54") (name "Net-(U9-IO2)") (class "Default")
      (node (ref "U13") (pin "1") (pinfunction "1_1") (pintype "unspecified"))
      (node (ref "U9") (pin "3") (pinfunction "IO2_3") (pintype "unspecified"))
    )
    (net (code "55") (name "Net-(U9-IO3)") (class "Default")
      (node (ref "U11") (pin "1") (pinfunction "1_1") (pintype "unspecified"))
      (node (ref "U9") (pin "7") (pinfunction "IO3_7") (pintype "unspecified"))
    )
    (net (code "56") (name "Net-(U18-A)") (class "Default")
      (node (ref "U17") (pin "2") (pinfunction "2_2") (pintype "unspecified"))
      (node (ref "U18") (pin "1") (pinfunction "A_1") (pintype "unspecified"))
    )
    (net (code "57") (name "RED") (class "Default")
      (node (ref "U1") (pin "25") (pinfunction "PB0_25") (pintype "unspecified"))
      (node (ref "U20") (pin "1") (pinfunction "1_1") (pintype "unspecified"))
    )
    (net (code "58") (name "SCK_BARO") (class "Default")
      (node (ref "U1") (pin "21") (pinfunction "PA5_21") (pintype "unspecified"))
      (node (ref "U4") (pin "4") (pinfunction "SCK_4") (pintype "unspecified"))
    )
    (net (code "59") (name "SCK_FLASH") (class "Default")
      (node (ref "U1") (pin "34") (pinfunction "PB13_34") (pintype "unspecified"))
      (node (ref "U9") (pin "2") (pinfunction "DO_2") (pintype "unspecified"))
    )
    (net (code "60") (name "SD_DAT0") (class "Default")
      (node (ref "U1") (pin "39") (pinfunction "PC8_39") (pintype "unspecified"))
      (node (ref "U33") (pin "7") (pinfunction "DAT0_7") (pintype "unspecified"))
    )
    (net (code "61") (name "SD_DAT1") (class "Default")
      (node (ref "U1") (pin "40") (pinfunction "PC9_40") (pintype "unspecified"))
      (node (ref "U33") (pin "8") (pinfunction "DAT1_8") (pintype "unspecified"))
    )
    (net (code "62") (name "SD_DAT2") (class "Default")
      (node (ref "U1") (pin "51") (pinfunction "PC10_51") (pintype "unspecified"))
      (node (ref "U33") (pin "1") (pinfunction "DAT2_1") (pintype "unspecified"))
    )
    (net (code "63") (name "SD_DAT3") (class "Default")
      (node (ref "U1") (pin "52") (pinfunction "PC11_52") (pintype "unspecified"))
      (node (ref "U33") (pin "2") (pinfunction "CD/DAT3_2") (pintype "unspecified"))
    )
    (net (code "64") (name "SWCLK") (class "Default")
      (node (ref "H3") (pin "4") (pinfunction "4_4") (pintype "unspecified"))
      (node (ref "U1") (pin "49") (pinfunction "PA14_49") (pintype "unspecified"))
    )
    (net (code "65") (name "SWDIO") (class "Default")
      (node (ref "H3") (pin "3") (pinfunction "3_3") (pintype "unspecified"))
      (node (ref "U1") (pin "46") (pinfunction "PA13_46") (pintype "unspecified"))
    )
    (net (code "66") (name "VDD") (class "Default")
      (node (ref "C13") (pin "2") (pinfunction "2_2") (pintype "unspecified"))
      (node (ref "C7") (pin "2") (pinfunction "2_2") (pintype "unspecified"))
      (node (ref "CN1") (pin "1") (pinfunction "1_1") (pintype "unspecified"))
      (node (ref "H3") (pin "1") (pinfunction "1_1") (pintype "unspecified"))
      (node (ref "LED1") (pin "3") (pinfunction "A_3") (pintype "unspecified"))
      (node (ref "U1") (pin "1") (pinfunction "VBAT_1") (pintype "unspecified"))
      (node (ref "U1") (pin "13") (pinfunction "VDDA_13") (pintype "unspecified"))
      (node (ref "U1") (pin "19") (pinfunction "VDD_19") (pintype "unspecified"))
      (node (ref "U1") (pin "32") (pinfunction "VDD_32") (pintype "unspecified"))
      (node (ref "U1") (pin "48") (pinfunction "VDD_48") (pintype "unspecified"))
      (node (ref "U1") (pin "64") (pinfunction "VDD_64") (pintype "unspecified"))
      (node (ref "U11") (pin "2") (pinfunction "2_2") (pintype "unspecified"))
      (node (ref "U13") (pin "2") (pinfunction "2_2") (pintype "unspecified"))
      (node (ref "U2") (pin "4") (pinfunction "VOUT_4") (pintype "unspecified"))
      (node (ref "U3") (pin "13") (pinfunction "VDD_13") (pintype "unspecified"))
      (node (ref "U33") (pin "4") (pinfunction "VDD_4") (pintype "unspecified"))
      (node (ref "U9") (pin "8") (pinfunction "VCC_8") (pintype "unspecified"))
    )
    (net (code "67") (name "unconnected-(CN1-Pad4)") (class "Default")
      (node (ref "CN1") (pin "4") (pinfunction "4_4") (pintype "unspecified+no_connect"))
    )
    (net (code "68") (name "unconnected-(CN1-Pad5)") (class "Default")
      (node (ref "CN1") (pin "5") (pinfunction "5_5") (pintype "unspecified+no_connect"))
    )
    (net (code "69") (name "unconnected-(CN1-Pad6)") (class "Default")
      (node (ref "CN1") (pin "6") (pinfunction "6_6") (pintype "unspecified+no_connect"))
    )
    (net (code "70") (name "unconnected-(CN1-Pad7)") (class "Default")
      (node (ref "CN1") (pin "7") (pinfunction "7_7") (pintype "unspecified+no_connect"))
    )
    (net (code "71") (name "unconnected-(CN1-Pad9)") (class "Default")
      (node (ref "CN1") (pin "9") (pinfunction "9_9") (pintype "unspecified+no_connect"))
    )
    (net (code "72") (name "unconnected-(CN1-Pad10)") (class "Default")
      (node (ref "CN1") (pin "10") (pinfunction "10_10") (pintype "unspecified+no_connect"))
    )
    (net (code "73") (name "unconnected-(CN1-Pad11)") (class "Default")
      (node (ref "CN1") (pin "11") (pinfunction "11_11") (pintype "unspecified+no_connect"))
    )
    (net (code "74") (name "unconnected-(CN1-Pad12)") (class "Default")
      (node (ref "CN1") (pin "12") (pinfunction "12_12") (pintype "unspecified+no_connect"))
    )
    (net (code "75") (name "unconnected-(U1-NRST-Pad7)") (class "Default")
      (node (ref "U1") (pin "7") (pinfunction "NRST_7") (pintype "unspecified+no_connect"))
    )
    (net (code "76") (name "unconnected-(U1-PA15-Pad50)") (class "Default")
      (node (ref "U1") (pin "50") (pinfunction "PA15_50") (pintype "unspecified+no_connect"))
    )
    (net (code "77") (name "unconnected-(U1-PB2-Pad27)") (class "Default")
      (node (ref "U1") (pin "27") (pinfunction "PB2_27") (pintype "unspecified+no_connect"))
    )
    (net (code "78") (name "unconnected-(U1-PB3-Pad55)") (class "Default")
      (node (ref "U1") (pin "55") (pinfunction "PB3_55") (pintype "unspecified+no_connect"))
    )
    (net (code "79") (name "unconnected-(U1-PB5-Pad57)") (class "Default")
      (node (ref "U1") (pin "57") (pinfunction "PB5_57") (pintype "unspecified+no_connect"))
    )
    (net (code "80") (name "unconnected-(U1-PB8-Pad61)") (class "Default")
      (node (ref "U1") (pin "61") (pinfunction "PB8_61") (pintype "unspecified+no_connect"))
    )
    (net (code "81") (name "unconnected-(U1-PB9-Pad62)") (class "Default")
      (node (ref "U1") (pin "62") (pinfunction "PB9_62") (pintype "unspecified+no_connect"))
    )
    (net (code "82") (name "unconnected-(U1-PB10-Pad28)") (class "Default")
      (node (ref "U1") (pin "28") (pinfunction "PB10_28") (pintype "unspecified+no_connect"))
    )
    (net (code "83") (name "unconnected-(U1-PB11-Pad29)") (class "Default")
      (node (ref "U1") (pin "29") (pinfunction "PB11_29") (pintype "unspecified+no_connect"))
    )
    (net (code "84") (name "unconnected-(U1-PB12-Pad33)") (class "Default")
      (node (ref "U1") (pin "33") (pinfunction "PB12_33") (pintype "unspecified+no_connect"))
    )
    (net (code "85") (name "unconnected-(U1-PC0-Pad8)") (class "Default")
      (node (ref "U1") (pin "8") (pinfunction "PC0_8") (pintype "unspecified+no_connect"))
    )
    (net (code "86") (name "unconnected-(U1-PC1-Pad9)") (class "Default")
      (node (ref "U1") (pin "9") (pinfunction "PC1_9") (pintype "unspecified+no_connect"))
    )
    (net (code "87") (name "unconnected-(U1-PC2-Pad10)") (class "Default")
      (node (ref "U1") (pin "10") (pinfunction "PC2_10") (pintype "unspecified+no_connect"))
    )
    (net (code "88") (name "unconnected-(U1-PC3-Pad11)") (class "Default")
      (node (ref "U1") (pin "11") (pinfunction "PC3_11") (pintype "unspecified+no_connect"))
    )
    (net (code "89") (name "unconnected-(U1-PC4-Pad24)") (class "Default")
      (node (ref "U1") (pin "24") (pinfunction "PC4_24") (pintype "unspecified+no_connect"))
    )
    (net (code "90") (name "unconnected-(U1-PC6-Pad37)") (class "Default")
      (node (ref "U1") (pin "37") (pinfunction "PC6_37") (pintype "unspecified+no_connect"))
    )
    (net (code "91") (name "unconnected-(U1-PC7-Pad38)") (class "Default")
      (node (ref "U1") (pin "38") (pinfunction "PC7_38") (pintype "unspecified+no_connect"))
    )
    (net (code "92") (name "unconnected-(U1-PC13-Pad2)") (class "Default")
      (node (ref "U1") (pin "2") (pinfunction "PC13_2") (pintype "unspecified+no_connect"))
    )
    (net (code "93") (name "unconnected-(U1-PC14-OSC32_IN-Pad3)") (class "Default")
      (node (ref "U1") (pin "3") (pinfunction "PC14-OSC32_IN_3") (pintype "unspecified+no_connect"))
    )
    (net (code "94") (name "unconnected-(U1-PC15-OSC32_OUT-Pad4)") (class "Default")
      (node (ref "U1") (pin "4") (pinfunction "PC15-OSC32_OUT_4") (pintype "unspecified+no_connect"))
    )
    (net (code "95") (name "unconnected-(U2-VOUT-Pad2)") (class "Default")
      (node (ref "U2") (pin "2") (pinfunction "VOUT_2") (pintype "unspecified+no_connect"))
    )
    (net (code "96") (name "unconnected-(U3-AD0-Pad9)") (class "Default")
      (node (ref "U3") (pin "9") (pinfunction "AD0_9") (pintype "unspecified+no_connect"))
    )
    (net (code "97") (name "unconnected-(U3-AUX_CL-Pad7)") (class "Default")
      (node (ref "U3") (pin "7") (pinfunction "AUX_CL_7") (pintype "unspecified+no_connect"))
    )
    (net (code "98") (name "unconnected-(U3-AUX_DA-Pad6)") (class "Default")
      (node (ref "U3") (pin "6") (pinfunction "AUX_DA_6") (pintype "unspecified+no_connect"))
    )
    (net (code "99") (name "unconnected-(U3-EP-Pad25)") (class "Default")
      (node (ref "U3") (pin "25") (pinfunction "EP_25") (pintype "unspecified+no_connect"))
    )
    (net (code "100") (name "unconnected-(U3-INT-Pad12)") (class "Default")
      (node (ref "U3") (pin "12") (pinfunction "INT_12") (pintype "unspecified+no_connect"))
    )
    (net (code "101") (name "unconnected-(U3-NC-Pad2)") (class "Default")
      (node (ref "U3") (pin "2") (pinfunction "NC_2") (pintype "unspecified+no_connect"))
    )
    (net (code "102") (name "unconnected-(U3-NC-Pad3)") (class "Default")
      (node (ref "U3") (pin "3") (pinfunction "NC_3") (pintype "unspecified+no_connect"))
    )
    (net (code "103") (name "unconnected-(U3-NC-Pad4)") (class "Default")
      (node (ref "U3") (pin "4") (pinfunction "NC_4") (pintype "unspecified+no_connect"))
    )
    (net (code "104") (name "unconnected-(U3-NC-Pad5)") (class "Default")
      (node (ref "U3") (pin "5") (pinfunction "NC_5") (pintype "unspecified+no_connect"))
    )
    (net (code "105") (name "unconnected-(U3-NC-Pad14)") (class "Default")
      (node (ref "U3") (pin "14") (pinfunction "NC_14") (pintype "unspecified+no_connect"))
    )
    (net (code "106") (name "unconnected-(U3-NC-Pad15)") (class "Default")
      (node (ref "U3") (pin "15") (pinfunction "NC_15") (pintype "unspecified+no_connect"))
    )
    (net (code "107") (name "unconnected-(U3-NC-Pad16)") (class "Default")
      (node (ref "U3") (pin "16") (pinfunction "NC_16") (pintype "unspecified+no_connect"))
    )
    (net (code "108") (name "unconnected-(U3-NC-Pad17)") (class "Default")
      (node (ref "U3") (pin "17") (pinfunction "NC_17") (pintype "unspecified+no_connect"))
    )
    (net (code "109") (name "unconnected-(U3-RESV-Pad19)") (class "Default")
      (node (ref "U3") (pin "19") (pinfunction "RESV_19") (pintype "unspecified+no_connect"))
    )
    (net (code "110") (name "unconnected-(U3-RESV-Pad21)") (class "Default")
      (node (ref "U3") (pin "21") (pinfunction "RESV_21") (pintype "unspecified+no_connect"))
    )
    (net (code "111") (name "unconnected-(U3-RESV-Pad22)") (class "Default")
      (node (ref "U3") (pin "22") (pinfunction "RESV_22") (pintype "unspecified+no_connect"))
    )
    (net (code "112") (name "unconnected-(U3-VLOGIC-Pad8)") (class "Default")
      (node (ref "U3") (pin "8") (pinfunction "VLOGIC_8") (pintype "unspecified+no_connect"))
    )
    (net (code "113") (name "unconnected-(U5-EN-Pad3)") (class "Default")
      (node (ref "U5") (pin "3") (pinfunction "EN_3") (pintype "unspecified+no_connect"))
    )
    (net (code "114") (name "unconnected-(U5-EP-Pad9)") (class "Default")
      (node (ref "U5") (pin "9") (pinfunction "EP_9") (pintype "unspecified+no_connect"))
    )
    (net (code "115") (name "unconnected-(U6-ID-Pad4)") (class "Default")
      (node (ref "U6") (pin "4") (pinfunction "ID_4") (pintype "unspecified+no_connect"))
    )
    (net (code "116") (name "unconnected-(U33-Pad0)") (class "Default")
      (node (ref "U33") (pin "0") (pinfunction "0_0") (pintype "unspecified+no_connect"))
    )
    (net (code "117") (name "unconnected-(U33-PadCD)") (class "Default")
      (node (ref "U33") (pin "CD") (pinfunction "CD_CD") (pintype "unspecified+no_connect"))
    )
  )
)
